# untitled.net
KiCad netlist of a schematic drawn in EAGLE
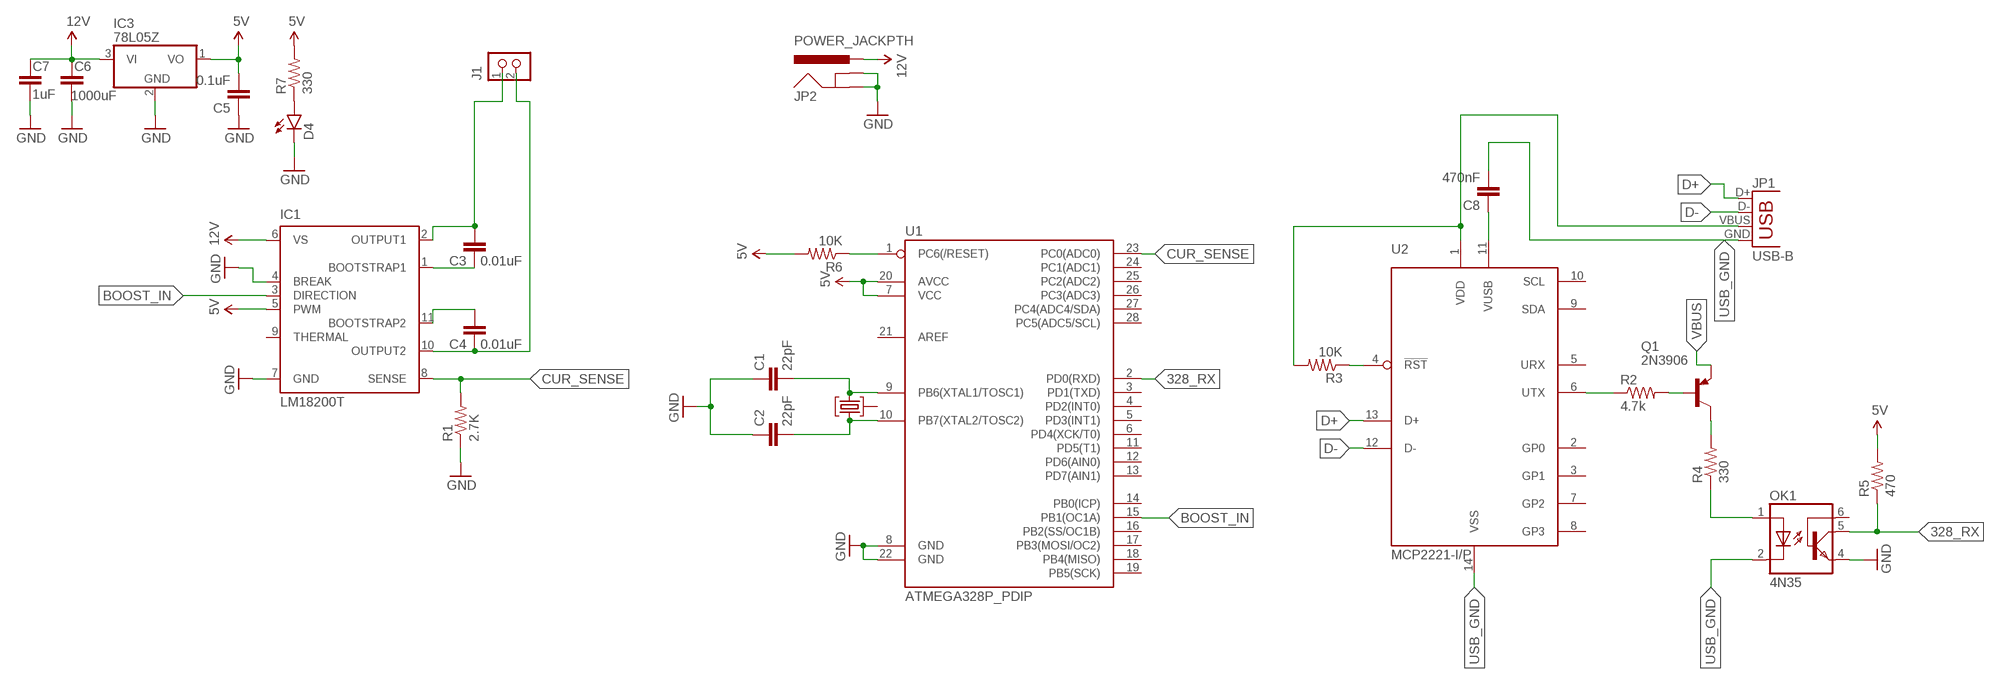
[diagram p0: schematic, sheet 1]

(export (version "E")
  (design (tool "Eeschema 10.0.6"))
  (components
    (comp (ref "C1")
      (value "22pF")
      (footprint "eagle-import:CAP-PTH-SMALLEZ")
      (fields (field (name "MF") "MURATA") (field (name "MPN") "DEC1X3J220JC4B"))
      (libsource (lib "eagle-import") (part "CAPEZ"))
    )
    (comp (ref "C2")
      (value "22pF")
      (footprint "eagle-import:CAP-PTH-SMALLEZ")
      (fields (field (name "MF") "MURATA") (field (name "MPN") "DEC1X3J220JC4B"))
      (libsource (lib "eagle-import") (part "CAPEZ"))
    )
    (comp (ref "C3")
      (value "0.01uF")
      (footprint "eagle-import:CAP-PTH-SMALLEZ")
      (fields (field (name "MF") "VISHAY BC COMPONENTS") (field (name "MPN") "D103K43Y5PH63L2R"))
      (libsource (lib "eagle-import") (part "CAPEZ"))
    )
    (comp (ref "C4")
      (value "0.01uF")
      (footprint "eagle-import:CAP-PTH-SMALLEZ")
      (fields (field (name "MF") "VISHAY BC COMPONENTS") (field (name "MPN") "D103K43Y5PH63L2R"))
      (libsource (lib "eagle-import") (part "CAPEZ"))
    )
    (comp (ref "C5")
      (value "0.1uF")
      (footprint "eagle-import:CAP-PTH-SMALLEZ")
      (fields (field (name "MF") "MULTICOMP") (field (name "MPN") "MCRH100V104M5X11"))
      (libsource (lib "eagle-import") (part "CAPEZ"))
    )
    (comp (ref "C6")
      (value "1000uF")
      (footprint "eagle-import:CAP-PTH-SMALLEZ")
      (fields (field (name "MF") "MULTICOMP") (field (name "MPN") "MCGPR10V108M8X14"))
      (libsource (lib "eagle-import") (part "CAPEZ"))
    )
    (comp (ref "C7")
      (value "1uF")
      (footprint "eagle-import:CAP-PTH-SMALLEZ")
      (fields (field (name "MF") "MULTICOMP") (field (name "MPN") "MCNP16V105M5X11"))
      (libsource (lib "eagle-import") (part "CAPEZ"))
    )
    (comp (ref "C8")
      (value "470nF")
      (footprint "eagle-import:CAP-PTH-SMALLEZ")
      (fields (field (name "MF") "MULTICOMP") (field (name "MPN") "MCBU5471K5"))
      (libsource (lib "eagle-import") (part "CAPEZ"))
    )
    (comp (ref "D4")
      (value "LED-3MM-NO_SILK")
      (footprint "eagle-import:LED3MM-NS")
      (fields (field (name "MF") "MULTICOMP") (field (name "MPN") "MCL034MD"))
      (libsource (lib "eagle-import") (part "LED-3MM-NO_SILK"))
    )
    (comp (ref "IC1")
      (value "LM18200T")
      (footprint "eagle-import:TO-220-11")
      (fields
        (field (name "MF") "TEXAS INSTRUMENTS")
        (field (name "MPN") "LMD18200T/NOPB")
        (field (name "OC_FARNELL") "1468979")
      )
      (libsource (lib "eagle-import") (part "LM18200T"))
    )
    (comp (ref "IC3")
      (value "78L05Z")
      (footprint "eagle-import:TO92")
      (fields (field (name "MF") "STMICROELECTRONICS") (field (name "MPN") "L78L05ACZ"))
      (libsource (lib "eagle-import") (part "78ZL05"))
    )
    (comp (ref "J1")
      (value "CON_TERMINAL_BLOCK_02-5MM")
      (footprint "eagle-import:TERMINAL_BLOCK_2P_5")
      (fields (field (name "MF") "CAMDENBOSS") (field (name "MPN") "CTB0102/2"))
      (libsource (lib "eagle-import") (part "CON_TERMINAL_BLOCK_02-5MM"))
    )
    (comp (ref "JP1")
      (value "USB-B")
      (footprint "eagle-import:USB-B-PTH")
      (fields (field (name "MF") "MULTICOMP") (field (name "MPN") "USB-B-S-RA."))
      (libsource (lib "eagle-import") (part "USBPTH"))
    )
    (comp (ref "JP2")
      (value "POWER_JACKPTH")
      (footprint "eagle-import:POWER_JACK_PTH")
      (fields (field (name "MF") "CLIFF ELECTRONIC COMPONENTS") (field (name "MPN") "DC10A"))
      (libsource (lib "eagle-import") (part "POWER_JACKPTH"))
    )
    (comp (ref "OK1")
      (value "4N35")
      (footprint "eagle-import:DIL06")
      (fields (field (name "MF") "FAIRCHILD SEMICONDUCTOR") (field (name "MF_1") "VISHAY"))
      (libsource (lib "eagle-import") (part "4N35"))
    )
    (comp (ref "Q1")
      (value "2N3906")
      (footprint "eagle-import:TO92")
      (fields (field (name "MF") "MULTICOMP"))
      (libsource (lib "eagle-import") (part "2N3906"))
    )
    (comp (ref "QF1")
      (value "8M10AHC49T")
      (footprint "eagle-import:HC49U")
      (fields
        (field (name "MF") "EUROQUARTZ")
        (field (name "MPN") "16.000MHZ HC49/4H/30/50/40/18PF/ATF")
        (field (name "OC_FARNELL") "1640875")
      )
      (libsource (lib "eagle-import") (part "8M10AHC49T"))
    )
    (comp (ref "R1")
      (value "2.7K")
      (footprint "eagle-import:AXIAL-0.3")
      (fields (field (name "MF") "MULTICOMP") (field (name "MPN") "MCRE000042"))
      (libsource (lib "eagle-import") (part "RESISTORAXIAL-0.3"))
    )
    (comp (ref "R2")
      (value "4.7k")
      (footprint "eagle-import:AXIAL-0.3")
      (fields (field (name "MF") "MULTICOMP") (field (name "MPN") "MCRE000045"))
      (libsource (lib "eagle-import") (part "RESISTORAXIAL-0.3"))
    )
    (comp (ref "R3")
      (value "10K")
      (footprint "eagle-import:AXIAL-0.3")
      (fields (field (name "MF") "MULTICOMP") (field (name "MPN") "MCMF006FF1002A50"))
      (libsource (lib "eagle-import") (part "RESISTORAXIAL-0.3"))
    )
    (comp (ref "R4")
      (value "330")
      (footprint "eagle-import:AXIAL-0.3")
      (fields (field (name "MF") "MULTICOMP") (field (name "MPN") "MCRE000031"))
      (libsource (lib "eagle-import") (part "RESISTORAXIAL-0.3"))
    )
    (comp (ref "R5")
      (value "470")
      (footprint "eagle-import:AXIAL-0.3")
      (fields (field (name "MF") "MULTICOMP") (field (name "MPN") "MCRE000033"))
      (libsource (lib "eagle-import") (part "RESISTORAXIAL-0.3"))
    )
    (comp (ref "R6")
      (value "10K")
      (footprint "eagle-import:AXIAL-0.3")
      (fields (field (name "MF") "MULTICOMP") (field (name "MPN") "MCMF006FF1002A50"))
      (libsource (lib "eagle-import") (part "RESISTORAXIAL-0.3"))
    )
    (comp (ref "R7")
      (value "330")
      (footprint "eagle-import:AXIAL-0.3")
      (fields (field (name "MF") "MULTICOMP") (field (name "MPN") "MCRE000031"))
      (libsource (lib "eagle-import") (part "RESISTORAXIAL-0.3"))
    )
    (comp (ref "U1")
      (value "ATMEGA328P_PDIP")
      (footprint "eagle-import:DIL28-3")
      (fields (field (name "MF") "ATMEL") (field (name "MPN") "ATMEGA328P-PU"))
      (libsource (lib "eagle-import") (part "ATMEGA328P_PDIP"))
    )
    (comp (ref "U2")
      (value "MCP2221-I/P")
      (footprint "eagle-import:DIL14")
      (fields (field (name "MF") "MICROCHIP"))
      (libsource (lib "eagle-import") (part "MCP2221-I/P"))
    )
  )
  (nets
    (net (code "1") (name "5V") (class "Default")
      (node (ref "C5") (pin "2") (pinfunction "2_2") (pintype "passive"))
      (node (ref "IC1") (pin "5") (pinfunction "PWM_5") (pintype "input"))
      (node (ref "IC3") (pin "1") (pinfunction "VO_1") (pintype "passive"))
      (node (ref "R5") (pin "P$2") (pinfunction "2_P$2") (pintype "passive"))
      (node (ref "R6") (pin "P$2") (pinfunction "2_P$2") (pintype "passive"))
      (node (ref "R7") (pin "P$2") (pinfunction "2_P$2") (pintype "passive"))
      (node (ref "U1") (pin "20") (pinfunction "AVCC_20") (pintype "bidirectional"))
      (node (ref "U1") (pin "7") (pinfunction "VCC_7") (pintype "bidirectional"))
    )
    (net (code "2") (name "12V") (class "Default")
      (node (ref "C6") (pin "2") (pinfunction "2_2") (pintype "passive"))
      (node (ref "C7") (pin "2") (pinfunction "2_2") (pintype "passive"))
      (node (ref "IC1") (pin "6") (pinfunction "VS_6") (pintype "power_in"))
      (node (ref "IC3") (pin "3") (pinfunction "VI_3") (pintype "input"))
      (node (ref "JP2") (pin "PWR") (pinfunction "PWR_PWR") (pintype "bidirectional"))
    )
    (net (code "3") (name "328_RX") (class "Default")
      (node (ref "OK1") (pin "5") (pinfunction "COL_5") (pintype "passive"))
      (node (ref "R5") (pin "P$1") (pinfunction "1_P$1") (pintype "passive"))
      (node (ref "U1") (pin "2") (pinfunction "PD0(RXD)_2") (pintype "bidirectional"))
    )
    (net (code "4") (name "BOOST_IN") (class "Default")
      (node (ref "IC1") (pin "3") (pinfunction "DIRECTION_3") (pintype "input"))
      (node (ref "U1") (pin "15") (pinfunction "PB1(OC1A)_15") (pintype "bidirectional"))
    )
    (net (code "5") (name "CUR_SENSE") (class "Default")
      (node (ref "IC1") (pin "8") (pinfunction "SENSE_8") (pintype "output"))
      (node (ref "R1") (pin "P$2") (pinfunction "2_P$2") (pintype "passive"))
      (node (ref "U1") (pin "23") (pinfunction "PC0(ADC0)_23") (pintype "bidirectional"))
    )
    (net (code "6") (name "D+") (class "Default")
      (node (ref "JP1") (pin "D+") (pinfunction "D+_D+") (pintype "bidirectional"))
      (node (ref "U2") (pin "13") (pinfunction "D+_13") (pintype "bidirectional"))
    )
    (net (code "7") (name "D-") (class "Default")
      (node (ref "JP1") (pin "D-") (pinfunction "D-_D-") (pintype "bidirectional"))
      (node (ref "U2") (pin "12") (pinfunction "D-_12") (pintype "bidirectional"))
    )
    (net (code "8") (name "GND") (class "Default")
      (node (ref "C1") (pin "1") (pinfunction "1_1") (pintype "passive"))
      (node (ref "C2") (pin "1") (pinfunction "1_1") (pintype "passive"))
      (node (ref "C5") (pin "1") (pinfunction "1_1") (pintype "passive"))
      (node (ref "C6") (pin "1") (pinfunction "1_1") (pintype "passive"))
      (node (ref "C7") (pin "1") (pinfunction "1_1") (pintype "passive"))
      (node (ref "D4") (pin "K") (pinfunction "C_K") (pintype "passive"))
      (node (ref "IC1") (pin "4") (pinfunction "BREAK_4") (pintype "input"))
      (node (ref "IC1") (pin "7") (pinfunction "GND_7") (pintype "power_in"))
      (node (ref "IC3") (pin "2") (pinfunction "GND_2") (pintype "passive"))
      (node (ref "JP2") (pin "GND") (pinfunction "GND_GND") (pintype "bidirectional"))
      (node (ref "JP2") (pin "GNDBREAK") (pinfunction "GNDBREAK_GNDBREAK") (pintype "bidirectional"))
      (node (ref "OK1") (pin "4") (pinfunction "EMI_4") (pintype "passive"))
      (node (ref "R1") (pin "P$1") (pinfunction "1_P$1") (pintype "passive"))
      (node (ref "U1") (pin "22") (pinfunction "GND_22") (pintype "bidirectional"))
      (node (ref "U1") (pin "8") (pinfunction "GND_8") (pintype "bidirectional"))
    )
    (net (code "9") (name "Net-(IC1-BOOTSTRAP1)") (class "Default")
      (node (ref "C3") (pin "1") (pinfunction "1_1") (pintype "passive"))
      (node (ref "IC1") (pin "1") (pinfunction "BOOTSTRAP1_1") (pintype "input"))
    )
    (net (code "10") (name "Net-(IC1-BOOTSTRAP2)") (class "Default")
      (node (ref "C4") (pin "2") (pinfunction "2_2") (pintype "passive"))
      (node (ref "IC1") (pin "11") (pinfunction "BOOTSTRAP2_11") (pintype "input"))
    )
    (net (code "11") (name "Net-(IC1-OUTPUT1)") (class "Default")
      (node (ref "C3") (pin "2") (pinfunction "2_2") (pintype "passive"))
      (node (ref "IC1") (pin "2") (pinfunction "OUTPUT1_2") (pintype "output"))
      (node (ref "J1") (pin "1") (pinfunction "1_1") (pintype "passive"))
    )
    (net (code "12") (name "Net-(IC1-OUTPUT2)") (class "Default")
      (node (ref "C4") (pin "1") (pinfunction "1_1") (pintype "passive"))
      (node (ref "IC1") (pin "10") (pinfunction "OUTPUT2_10") (pintype "output"))
      (node (ref "J1") (pin "2") (pinfunction "2_2") (pintype "passive"))
    )
    (net (code "13") (name "Net-(OK1-A)") (class "Default")
      (node (ref "OK1") (pin "1") (pinfunction "A_1") (pintype "passive"))
      (node (ref "R4") (pin "P$1") (pinfunction "1_P$1") (pintype "passive"))
    )
    (net (code "14") (name "Net-(Q1-B)") (class "Default")
      (node (ref "Q1") (pin "2") (pinfunction "B_2") (pintype "passive"))
      (node (ref "R2") (pin "P$2") (pinfunction "2_P$2") (pintype "passive"))
    )
    (net (code "15") (name "Net-(Q1-C)") (class "Default")
      (node (ref "Q1") (pin "1") (pinfunction "C_1") (pintype "passive"))
      (node (ref "R4") (pin "P$2") (pinfunction "2_P$2") (pintype "passive"))
    )
    (net (code "16") (name "Net-(R2-1)") (class "Default")
      (node (ref "R2") (pin "P$1") (pinfunction "1_P$1") (pintype "passive"))
      (node (ref "U2") (pin "6") (pinfunction "UTX_6") (pintype "output"))
    )
    (net (code "17") (name "Net-(R3-1)") (class "Default")
      (node (ref "R3") (pin "P$1") (pinfunction "1_P$1") (pintype "passive"))
      (node (ref "U2") (pin "4") (pinfunction "~{RST}_4") (pintype "input"))
    )
    (net (code "18") (name "Net-(R6-1)") (class "Default")
      (node (ref "R6") (pin "P$1") (pinfunction "1_P$1") (pintype "passive"))
      (node (ref "U1") (pin "1") (pinfunction "PC6(/RESET)_1") (pintype "bidirectional"))
    )
    (net (code "19") (name "Net-(R7-1)") (class "Default")
      (node (ref "D4") (pin "A") (pinfunction "A_A") (pintype "passive"))
      (node (ref "R7") (pin "P$1") (pinfunction "1_P$1") (pintype "passive"))
    )
    (net (code "20") (name "Net-(U1-PB6(XTAL1{slash}TOSC1))") (class "Default")
      (node (ref "C1") (pin "2") (pinfunction "2_2") (pintype "passive"))
      (node (ref "QF1") (pin "3") (pinfunction "3_3") (pintype "passive"))
      (node (ref "U1") (pin "9") (pinfunction "PB6(XTAL1/TOSC1)_9") (pintype "bidirectional"))
    )
    (net (code "21") (name "Net-(U1-PB7(XTAL2{slash}TOSC2))") (class "Default")
      (node (ref "C2") (pin "2") (pinfunction "2_2") (pintype "passive"))
      (node (ref "QF1") (pin "1") (pinfunction "1_1") (pintype "passive"))
      (node (ref "U1") (pin "10") (pinfunction "PB7(XTAL2/TOSC2)_10") (pintype "bidirectional"))
    )
    (net (code "22") (name "Net-(U2-VUSB)") (class "Default")
      (node (ref "C8") (pin "1") (pinfunction "1_1") (pintype "passive"))
      (node (ref "U2") (pin "11") (pinfunction "VUSB_11") (pintype "power_in"))
    )
    (net (code "23") (name "USB_GND") (class "Default")
      (node (ref "C8") (pin "2") (pinfunction "2_2") (pintype "passive"))
      (node (ref "JP1") (pin "GND") (pinfunction "GND_GND") (pintype "bidirectional"))
      (node (ref "OK1") (pin "2") (pinfunction "C_2") (pintype "passive"))
      (node (ref "U2") (pin "14") (pinfunction "VSS_14") (pintype "power_in"))
    )
    (net (code "24") (name "VBUS") (class "Default")
      (node (ref "JP1") (pin "VBUS") (pinfunction "VBUS_VBUS") (pintype "bidirectional"))
      (node (ref "Q1") (pin "3") (pinfunction "E_3") (pintype "passive"))
      (node (ref "R3") (pin "P$2") (pinfunction "2_P$2") (pintype "passive"))
      (node (ref "U2") (pin "1") (pinfunction "VDD_1") (pintype "power_in"))
    )
    (net (code "25") (name "unconnected-(IC1-THERMAL-Pad9)") (class "Default")
      (node (ref "IC1") (pin "9") (pinfunction "THERMAL_9") (pintype "output"))
    )
    (net (code "26") (name "unconnected-(OK1-BAS-Pad6)") (class "Default")
      (node (ref "OK1") (pin "6") (pinfunction "BAS_6") (pintype "passive"))
    )
    (net (code "27") (name "unconnected-(QF1-Pad2)") (class "Default")
      (node (ref "QF1") (pin "2") (pinfunction "2_2") (pintype "passive"))
    )
    (net (code "28") (name "unconnected-(U1-AREF-Pad21)") (class "Default")
      (node (ref "U1") (pin "21") (pinfunction "AREF_21") (pintype "bidirectional"))
    )
    (net (code "29") (name "unconnected-(U1-PB0(ICP)-Pad14)") (class "Default")
      (node (ref "U1") (pin "14") (pinfunction "PB0(ICP)_14") (pintype "bidirectional"))
    )
    (net (code "30") (name "unconnected-(U1-PB2(SS{slash}OC1B)-Pad16)") (class "Default")
      (node (ref "U1") (pin "16") (pinfunction "PB2(SS/OC1B)_16") (pintype "bidirectional"))
    )
    (net (code "31") (name "unconnected-(U1-PB3(MOSI{slash}OC2)-Pad17)") (class "Default")
      (node (ref "U1") (pin "17") (pinfunction "PB3(MOSI/OC2)_17") (pintype "bidirectional"))
    )
    (net (code "32") (name "unconnected-(U1-PB4(MISO)-Pad18)") (class "Default")
      (node (ref "U1") (pin "18") (pinfunction "PB4(MISO)_18") (pintype "bidirectional"))
    )
    (net (code "33") (name "unconnected-(U1-PB5(SCK)-Pad19)") (class "Default")
      (node (ref "U1") (pin "19") (pinfunction "PB5(SCK)_19") (pintype "bidirectional"))
    )
    (net (code "34") (name "unconnected-(U1-PC1(ADC1)-Pad24)") (class "Default")
      (node (ref "U1") (pin "24") (pinfunction "PC1(ADC1)_24") (pintype "bidirectional"))
    )
    (net (code "35") (name "unconnected-(U1-PC2(ADC2)-Pad25)") (class "Default")
      (node (ref "U1") (pin "25") (pinfunction "PC2(ADC2)_25") (pintype "bidirectional"))
    )
    (net (code "36") (name "unconnected-(U1-PC3(ADC3)-Pad26)") (class "Default")
      (node (ref "U1") (pin "26") (pinfunction "PC3(ADC3)_26") (pintype "bidirectional"))
    )
    (net (code "37") (name "unconnected-(U1-PC4(ADC4{slash}SDA)-Pad27)") (class "Default")
      (node (ref "U1") (pin "27") (pinfunction "PC4(ADC4/SDA)_27") (pintype "bidirectional"))
    )
    (net (code "38") (name "unconnected-(U1-PC5(ADC5{slash}SCL)-Pad28)") (class "Default")
      (node (ref "U1") (pin "28") (pinfunction "PC5(ADC5/SCL)_28") (pintype "bidirectional"))
    )
    (net (code "39") (name "unconnected-(U1-PD1(TXD)-Pad3)") (class "Default")
      (node (ref "U1") (pin "3") (pinfunction "PD1(TXD)_3") (pintype "bidirectional"))
    )
    (net (code "40") (name "unconnected-(U1-PD2(INT0)-Pad4)") (class "Default")
      (node (ref "U1") (pin "4") (pinfunction "PD2(INT0)_4") (pintype "bidirectional"))
    )
    (net (code "41") (name "unconnected-(U1-PD3(INT1)-Pad5)") (class "Default")
      (node (ref "U1") (pin "5") (pinfunction "PD3(INT1)_5") (pintype "bidirectional"))
    )
    (net (code "42") (name "unconnected-(U1-PD4(XCK{slash}T0)-Pad6)") (class "Default")
      (node (ref "U1") (pin "6") (pinfunction "PD4(XCK/T0)_6") (pintype "bidirectional"))
    )
    (net (code "43") (name "unconnected-(U1-PD5(T1)-Pad11)") (class "Default")
      (node (ref "U1") (pin "11") (pinfunction "PD5(T1)_11") (pintype "bidirectional"))
    )
    (net (code "44") (name "unconnected-(U1-PD6(AIN0)-Pad12)") (class "Default")
      (node (ref "U1") (pin "12") (pinfunction "PD6(AIN0)_12") (pintype "bidirectional"))
    )
    (net (code "45") (name "unconnected-(U1-PD7(AIN1)-Pad13)") (class "Default")
      (node (ref "U1") (pin "13") (pinfunction "PD7(AIN1)_13") (pintype "bidirectional"))
    )
    (net (code "46") (name "unconnected-(U2-GP0-Pad2)") (class "Default")
      (node (ref "U2") (pin "2") (pinfunction "GP0_2") (pintype "bidirectional"))
    )
    (net (code "47") (name "unconnected-(U2-GP1-Pad3)") (class "Default")
      (node (ref "U2") (pin "3") (pinfunction "GP1_3") (pintype "bidirectional"))
    )
    (net (code "48") (name "unconnected-(U2-GP2-Pad7)") (class "Default")
      (node (ref "U2") (pin "7") (pinfunction "GP2_7") (pintype "bidirectional"))
    )
    (net (code "49") (name "unconnected-(U2-GP3-Pad8)") (class "Default")
      (node (ref "U2") (pin "8") (pinfunction "GP3_8") (pintype "bidirectional"))
    )
    (net (code "50") (name "unconnected-(U2-SCL-Pad10)") (class "Default")
      (node (ref "U2") (pin "10") (pinfunction "SCL_10") (pintype "output"))
    )
    (net (code "51") (name "unconnected-(U2-SDA-Pad9)") (class "Default")
      (node (ref "U2") (pin "9") (pinfunction "SDA_9") (pintype "bidirectional"))
    )
    (net (code "52") (name "unconnected-(U2-URX-Pad5)") (class "Default")
      (node (ref "U2") (pin "5") (pinfunction "URX_5") (pintype "input"))
    )
  )
)
